# FT232RL_only_pins.net
KiCad netlist of a schematic drawn in EAGLE
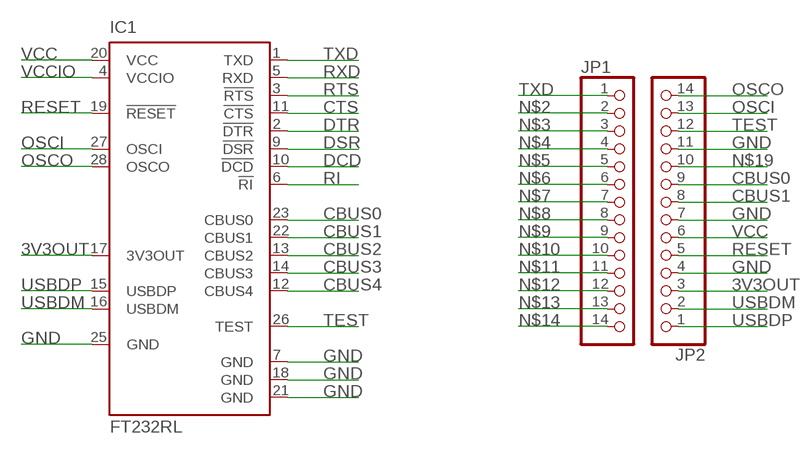
[diagram p0: schematic, sheet 1]

(export (version "E")
  (design (tool "Eeschema 10.0.6"))
  (components
    (comp (ref "IC1")
      (value "FT232RL")
      (footprint "eagle-import:SSOP28")
      (libsource (lib "eagle-import") (part "FT232RL"))
    )
    (comp (ref "JP1")
      (value "PINHD-1X14")
      (footprint "eagle-import:1X14")
      (libsource (lib "eagle-import") (part "PINHD-1X14"))
    )
    (comp (ref "JP2")
      (value "PINHD-1X14")
      (footprint "eagle-import:1X14")
      (libsource (lib "eagle-import") (part "PINHD-1X14"))
    )
  )
  (nets
    (net (code "1") (name "/3V3OUT") (class "Default")
      (node (ref "IC1") (pin "17") (pinfunction "3V3OUT_17") (pintype "output"))
      (node (ref "JP2") (pin "3") (pinfunction "3_3") (pintype "passive"))
    )
    (net (code "2") (name "/CBUS0") (class "Default")
      (node (ref "IC1") (pin "23") (pinfunction "CBUS0_23") (pintype "bidirectional"))
      (node (ref "JP2") (pin "9") (pinfunction "9_9") (pintype "passive"))
    )
    (net (code "3") (name "/CBUS1") (class "Default")
      (node (ref "IC1") (pin "22") (pinfunction "CBUS1_22") (pintype "bidirectional"))
      (node (ref "JP2") (pin "8") (pinfunction "8_8") (pintype "passive"))
    )
    (net (code "4") (name "/CBUS2") (class "Default")
      (node (ref "IC1") (pin "13") (pinfunction "CBUS2_13") (pintype "bidirectional"))
    )
    (net (code "5") (name "/CBUS3") (class "Default")
      (node (ref "IC1") (pin "14") (pinfunction "CBUS3_14") (pintype "bidirectional"))
    )
    (net (code "6") (name "/CBUS4") (class "Default")
      (node (ref "IC1") (pin "12") (pinfunction "CBUS4_12") (pintype "bidirectional"))
    )
    (net (code "7") (name "/CTS") (class "Default")
      (node (ref "IC1") (pin "11") (pinfunction "~{CTS}_11") (pintype "input"))
    )
    (net (code "8") (name "/DCD") (class "Default")
      (node (ref "IC1") (pin "10") (pinfunction "~{DCD}_10") (pintype "input"))
    )
    (net (code "9") (name "/DSR") (class "Default")
      (node (ref "IC1") (pin "9") (pinfunction "~{DSR}_9") (pintype "input"))
    )
    (net (code "10") (name "/DTR") (class "Default")
      (node (ref "IC1") (pin "2") (pinfunction "~{DTR}_2") (pintype "output"))
    )
    (net (code "11") (name "/GND") (class "Default")
      (node (ref "IC1") (pin "18") (pinfunction "GND_18") (pintype "power_in"))
      (node (ref "IC1") (pin "21") (pinfunction "GND_21") (pintype "power_in"))
      (node (ref "IC1") (pin "25") (pinfunction "GND_25") (pintype "power_in"))
      (node (ref "IC1") (pin "7") (pinfunction "GND_7") (pintype "power_in"))
      (node (ref "JP2") (pin "11") (pinfunction "11_11") (pintype "passive"))
      (node (ref "JP2") (pin "4") (pinfunction "4_4") (pintype "passive"))
      (node (ref "JP2") (pin "7") (pinfunction "7_7") (pintype "passive"))
    )
    (net (code "12") (name "/N$2") (class "Default")
      (node (ref "JP1") (pin "2") (pinfunction "2_2") (pintype "passive"))
    )
    (net (code "13") (name "/N$3") (class "Default")
      (node (ref "JP1") (pin "3") (pinfunction "3_3") (pintype "passive"))
    )
    (net (code "14") (name "/N$4") (class "Default")
      (node (ref "JP1") (pin "4") (pinfunction "4_4") (pintype "passive"))
    )
    (net (code "15") (name "/N$5") (class "Default")
      (node (ref "JP1") (pin "5") (pinfunction "5_5") (pintype "passive"))
    )
    (net (code "16") (name "/N$6") (class "Default")
      (node (ref "JP1") (pin "6") (pinfunction "6_6") (pintype "passive"))
    )
    (net (code "17") (name "/N$7") (class "Default")
      (node (ref "JP1") (pin "7") (pinfunction "7_7") (pintype "passive"))
    )
    (net (code "18") (name "/N$8") (class "Default")
      (node (ref "JP1") (pin "8") (pinfunction "8_8") (pintype "passive"))
    )
    (net (code "19") (name "/N$9") (class "Default")
      (node (ref "JP1") (pin "9") (pinfunction "9_9") (pintype "passive"))
    )
    (net (code "20") (name "/N$10") (class "Default")
      (node (ref "JP1") (pin "10") (pinfunction "10_10") (pintype "passive"))
    )
    (net (code "21") (name "/N$11") (class "Default")
      (node (ref "JP1") (pin "11") (pinfunction "11_11") (pintype "passive"))
    )
    (net (code "22") (name "/N$12") (class "Default")
      (node (ref "JP1") (pin "12") (pinfunction "12_12") (pintype "passive"))
    )
    (net (code "23") (name "/N$13") (class "Default")
      (node (ref "JP1") (pin "13") (pinfunction "13_13") (pintype "passive"))
    )
    (net (code "24") (name "/N$14") (class "Default")
      (node (ref "JP1") (pin "14") (pinfunction "14_14") (pintype "passive"))
    )
    (net (code "25") (name "/N$19") (class "Default")
      (node (ref "JP2") (pin "10") (pinfunction "10_10") (pintype "passive"))
    )
    (net (code "26") (name "/OSCI") (class "Default")
      (node (ref "IC1") (pin "27") (pinfunction "OSCI_27") (pintype "input"))
      (node (ref "JP2") (pin "13") (pinfunction "13_13") (pintype "passive"))
    )
    (net (code "27") (name "/OSCO") (class "Default")
      (node (ref "IC1") (pin "28") (pinfunction "OSCO_28") (pintype "output"))
      (node (ref "JP2") (pin "14") (pinfunction "14_14") (pintype "passive"))
    )
    (net (code "28") (name "/RESET") (class "Default")
      (node (ref "IC1") (pin "19") (pinfunction "~{RESET}_19") (pintype "input"))
      (node (ref "JP2") (pin "5") (pinfunction "5_5") (pintype "passive"))
    )
    (net (code "29") (name "/RI") (class "Default")
      (node (ref "IC1") (pin "6") (pinfunction "~{RI}_6") (pintype "input"))
    )
    (net (code "30") (name "/RTS") (class "Default")
      (node (ref "IC1") (pin "3") (pinfunction "~{RTS}_3") (pintype "output"))
    )
    (net (code "31") (name "/RXD") (class "Default")
      (node (ref "IC1") (pin "5") (pinfunction "RXD_5") (pintype "input"))
    )
    (net (code "32") (name "/TEST") (class "Default")
      (node (ref "IC1") (pin "26") (pinfunction "TEST_26") (pintype "input"))
      (node (ref "JP2") (pin "12") (pinfunction "12_12") (pintype "passive"))
    )
    (net (code "33") (name "/TXD") (class "Default")
      (node (ref "IC1") (pin "1") (pinfunction "TXD_1") (pintype "output"))
      (node (ref "JP1") (pin "1") (pinfunction "1_1") (pintype "passive"))
    )
    (net (code "34") (name "/USBDM") (class "Default")
      (node (ref "IC1") (pin "16") (pinfunction "USBDM_16") (pintype "bidirectional"))
      (node (ref "JP2") (pin "2") (pinfunction "2_2") (pintype "passive"))
    )
    (net (code "35") (name "/USBDP") (class "Default")
      (node (ref "IC1") (pin "15") (pinfunction "USBDP_15") (pintype "bidirectional"))
      (node (ref "JP2") (pin "1") (pinfunction "1_1") (pintype "passive"))
    )
    (net (code "36") (name "/VCC") (class "Default")
      (node (ref "IC1") (pin "20") (pinfunction "VCC_20") (pintype "power_in"))
      (node (ref "JP2") (pin "6") (pinfunction "6_6") (pintype "passive"))
    )
    (net (code "37") (name "/VCCIO") (class "Default")
      (node (ref "IC1") (pin "4") (pinfunction "VCCIO_4") (pintype "power_in"))
    )
  )
)
